# IR_Board.net
KiCad netlist of a schematic drawn in EAGLE
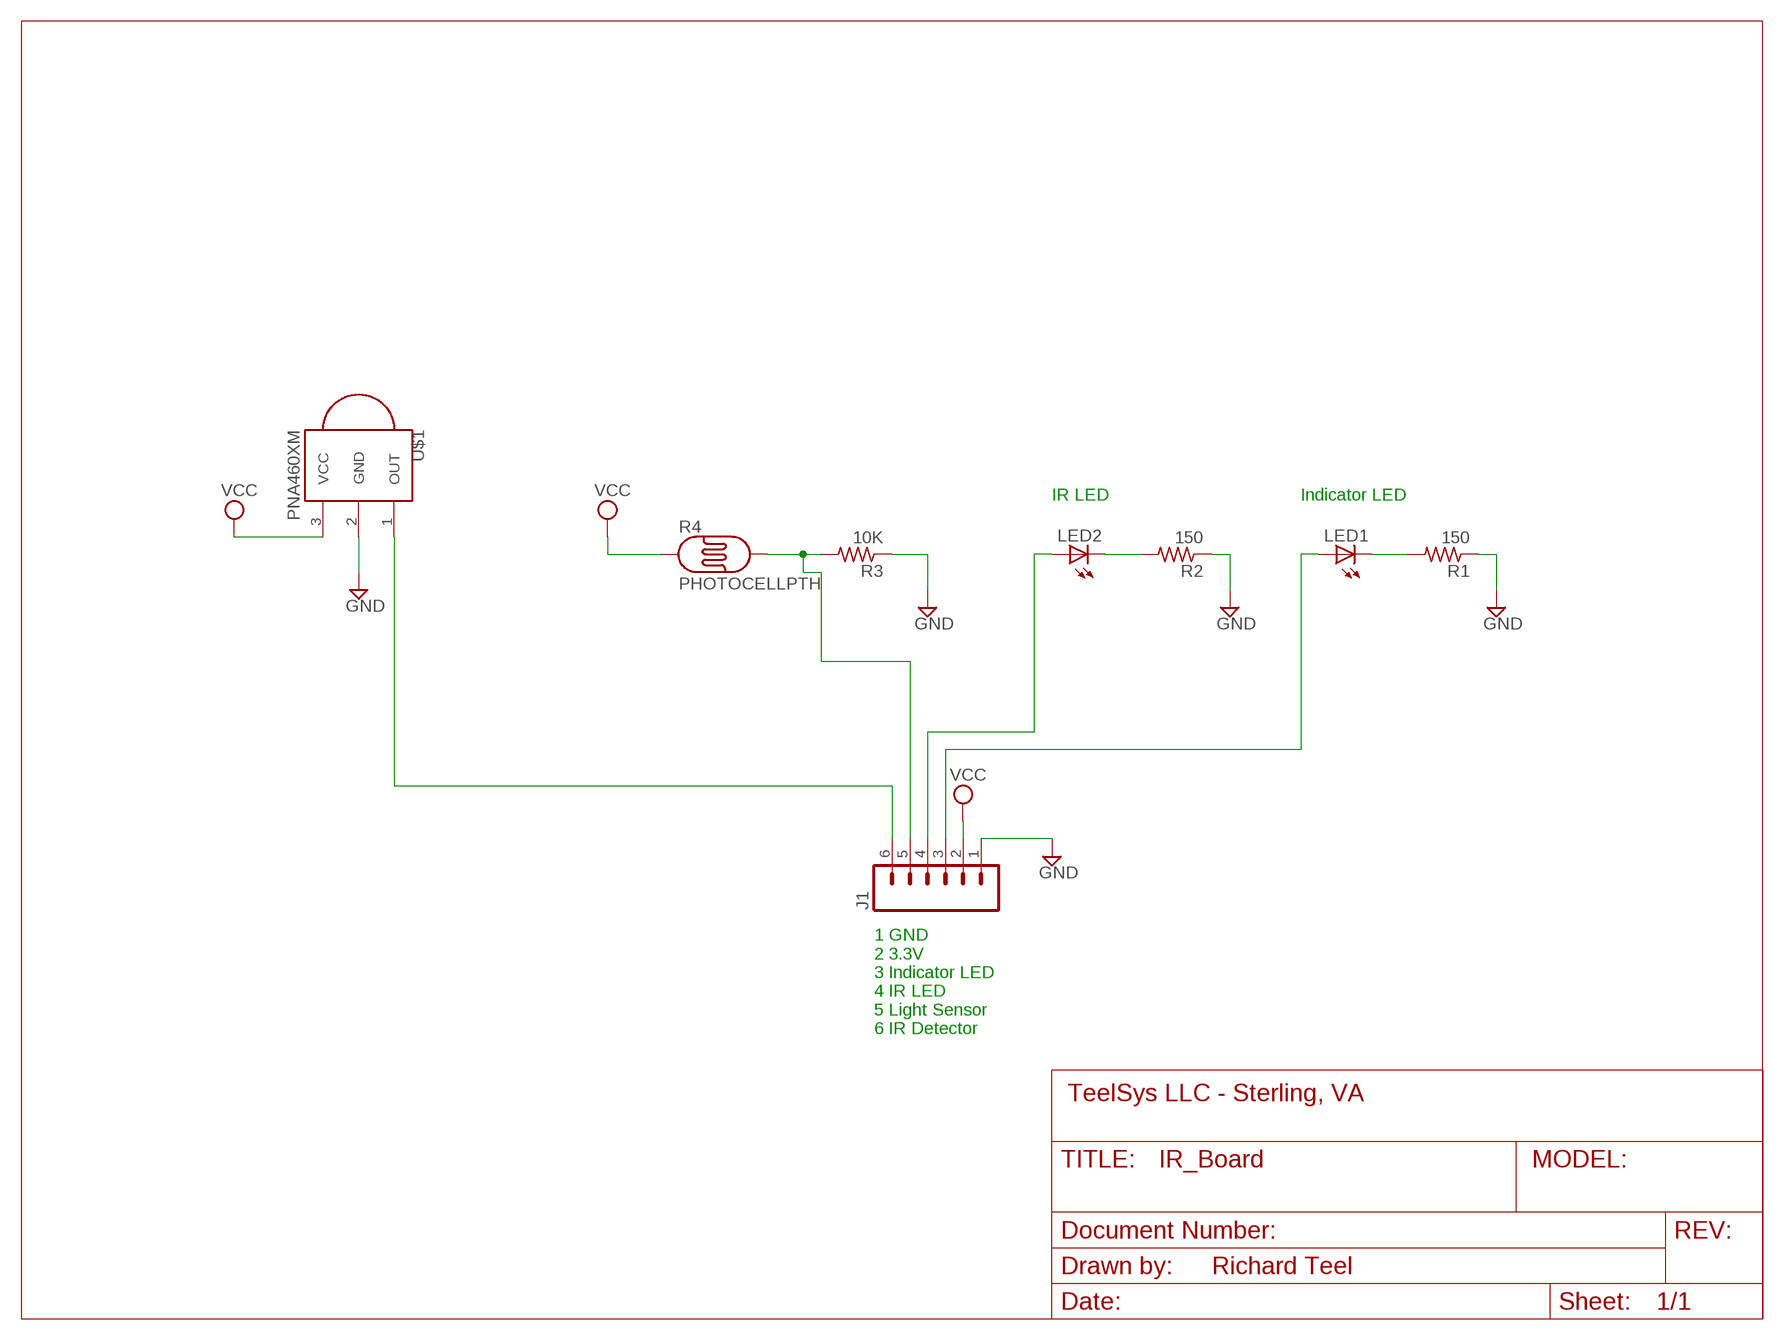
[diagram p0: schematic, sheet 1]

(export (version "E")
  (design (tool "Eeschema 10.0.6"))
  (components
    (comp (ref "J1")
      (value "M06LONGPADS")
      (footprint "eagle-import:1X06_LONGPADS")
      (libsource (lib "eagle-import") (part "M06LONGPADS"))
    )
    (comp (ref "LED1")
      (value "LED3MM")
      (footprint "eagle-import:LED3MM")
      (libsource (lib "eagle-import") (part "LED3MM"))
    )
    (comp (ref "LED2")
      (value "LED5MM")
      (footprint "eagle-import:LED5MM")
      (libsource (lib "eagle-import") (part "LED5MM"))
    )
    (comp (ref "R1")
      (value "150")
      (footprint "eagle-import:M0805")
      (libsource (lib "eagle-import") (part "R-US_M0805"))
    )
    (comp (ref "R2")
      (value "150")
      (footprint "eagle-import:M0805")
      (libsource (lib "eagle-import") (part "R-US_M0805"))
    )
    (comp (ref "R3")
      (value "10K")
      (footprint "eagle-import:M0805")
      (libsource (lib "eagle-import") (part "R-US_M0805"))
    )
    (comp (ref "R4")
      (value "PHOTOCELLPTH")
      (footprint "eagle-import:PHOTOCELL")
      (libsource (lib "eagle-import") (part "PHOTOCELLPTH"))
    )
    (comp (ref "U$1")
      (value "PNA460XM")
      (footprint "eagle-import:PNA460XM")
      (libsource (lib "eagle-import") (part "PNA460XM"))
    )
  )
  (nets
    (net (code "1") (name "GND") (class "Default")
      (node (ref "J1") (pin "1") (pinfunction "1_1") (pintype "passive"))
      (node (ref "R1") (pin "1") (pinfunction "1_1") (pintype "passive"))
      (node (ref "R2") (pin "1") (pinfunction "1_1") (pintype "passive"))
      (node (ref "R3") (pin "1") (pinfunction "1_1") (pintype "passive"))
      (node (ref "U$1") (pin "2") (pinfunction "GND_2") (pintype "power_in"))
    )
    (net (code "2") (name "Net-(J1-Pad3)") (class "Default")
      (node (ref "J1") (pin "3") (pinfunction "3_3") (pintype "passive"))
      (node (ref "LED1") (pin "A") (pinfunction "A_A") (pintype "passive"))
    )
    (net (code "3") (name "Net-(J1-Pad4)") (class "Default")
      (node (ref "J1") (pin "4") (pinfunction "4_4") (pintype "passive"))
      (node (ref "LED2") (pin "A") (pinfunction "A_A") (pintype "passive"))
    )
    (net (code "4") (name "Net-(LED1-C)") (class "Default")
      (node (ref "LED1") (pin "K") (pinfunction "C_K") (pintype "passive"))
      (node (ref "R1") (pin "2") (pinfunction "2_2") (pintype "passive"))
    )
    (net (code "5") (name "Net-(LED2-C)") (class "Default")
      (node (ref "LED2") (pin "K") (pinfunction "C_K") (pintype "passive"))
      (node (ref "R2") (pin "2") (pinfunction "2_2") (pintype "passive"))
    )
    (net (code "6") (name "Net-(R4-P$2)") (class "Default")
      (node (ref "J1") (pin "5") (pinfunction "5_5") (pintype "passive"))
      (node (ref "R3") (pin "2") (pinfunction "2_2") (pintype "passive"))
      (node (ref "R4") (pin "2") (pinfunction "P$2_2") (pintype "bidirectional"))
    )
    (net (code "7") (name "Net-(U$1-OUT)") (class "Default")
      (node (ref "J1") (pin "6") (pinfunction "6_6") (pintype "passive"))
      (node (ref "U$1") (pin "1") (pinfunction "OUT_1") (pintype "output"))
    )
    (net (code "8") (name "VCC") (class "Default")
      (node (ref "J1") (pin "2") (pinfunction "2_2") (pintype "passive"))
      (node (ref "R4") (pin "1") (pinfunction "P$1_1") (pintype "bidirectional"))
      (node (ref "U$1") (pin "3") (pinfunction "VCC_3") (pintype "power_in"))
    )
  )
)
